# SwitchesStepAtten.net
KiCad netlist of a schematic drawn in EAGLE
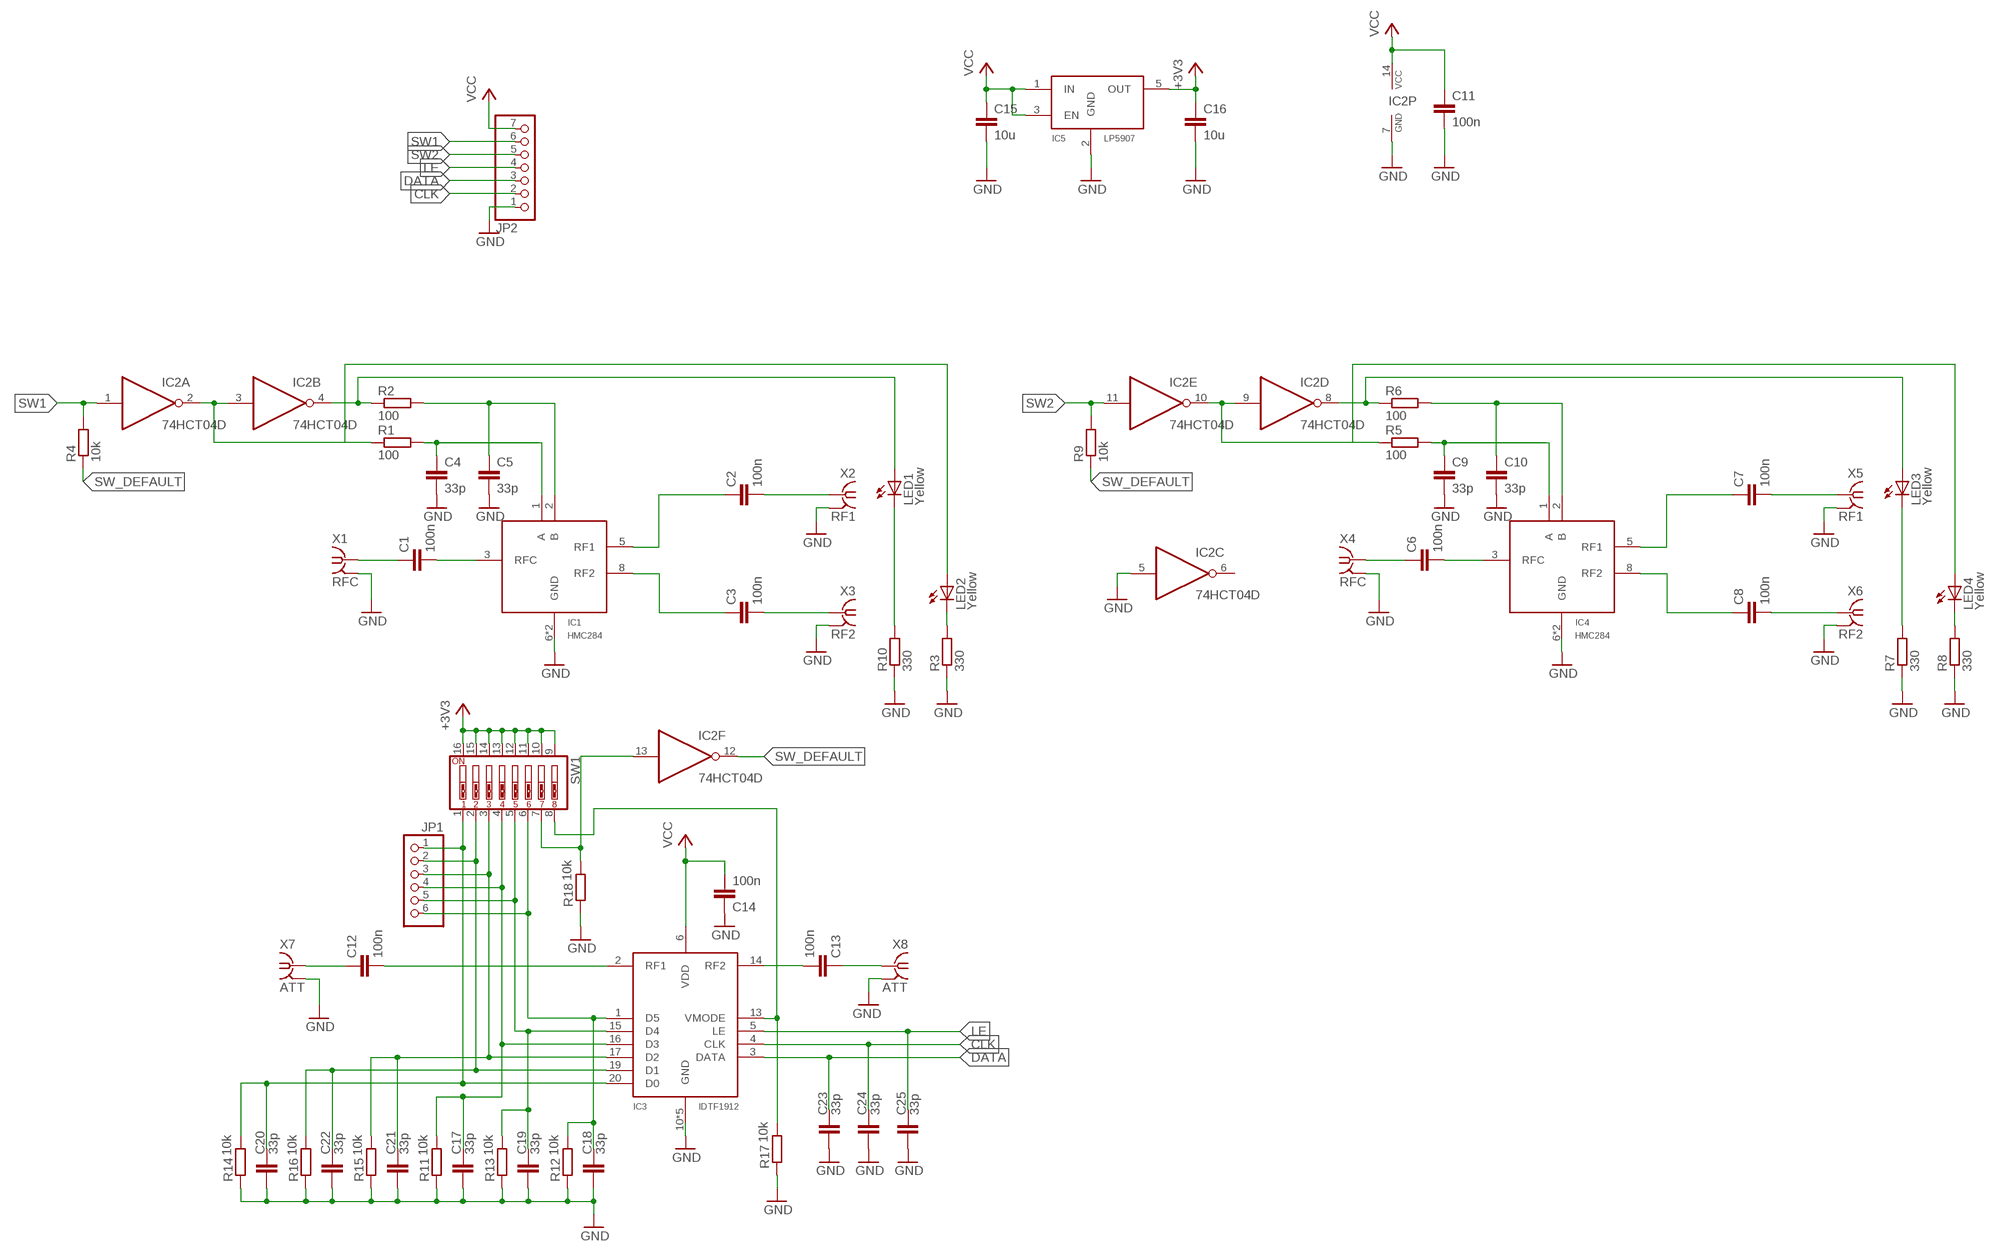
[diagram p0: schematic, sheet 1]

(export (version "E")
  (design (tool "Eeschema 10.0.6"))
  (components
    (comp (ref "C1")
      (value "100n")
      (footprint "eagle-import:C0603")
      (libsource (lib "eagle-import") (part "C-EUC0603"))
    )
    (comp (ref "C2")
      (value "100n")
      (footprint "eagle-import:C0603")
      (libsource (lib "eagle-import") (part "C-EUC0603"))
    )
    (comp (ref "C3")
      (value "100n")
      (footprint "eagle-import:C0603")
      (libsource (lib "eagle-import") (part "C-EUC0603"))
    )
    (comp (ref "C4")
      (value "33p")
      (footprint "eagle-import:C0603")
      (libsource (lib "eagle-import") (part "C-EUC0603"))
    )
    (comp (ref "C5")
      (value "33p")
      (footprint "eagle-import:C0603")
      (libsource (lib "eagle-import") (part "C-EUC0603"))
    )
    (comp (ref "C6")
      (value "100n")
      (footprint "eagle-import:C0603")
      (libsource (lib "eagle-import") (part "C-EUC0603"))
    )
    (comp (ref "C7")
      (value "100n")
      (footprint "eagle-import:C0603")
      (libsource (lib "eagle-import") (part "C-EUC0603"))
    )
    (comp (ref "C8")
      (value "100n")
      (footprint "eagle-import:C0603")
      (libsource (lib "eagle-import") (part "C-EUC0603"))
    )
    (comp (ref "C9")
      (value "33p")
      (footprint "eagle-import:C0603")
      (libsource (lib "eagle-import") (part "C-EUC0603"))
    )
    (comp (ref "C10")
      (value "33p")
      (footprint "eagle-import:C0603")
      (libsource (lib "eagle-import") (part "C-EUC0603"))
    )
    (comp (ref "C11")
      (value "100n")
      (footprint "eagle-import:C0603")
      (libsource (lib "eagle-import") (part "C-EUC0603"))
    )
    (comp (ref "C12")
      (value "100n")
      (footprint "eagle-import:C0603")
      (libsource (lib "eagle-import") (part "C-EUC0603"))
    )
    (comp (ref "C13")
      (value "100n")
      (footprint "eagle-import:C0603")
      (libsource (lib "eagle-import") (part "C-EUC0603"))
    )
    (comp (ref "C14")
      (value "100n")
      (footprint "eagle-import:C0603")
      (libsource (lib "eagle-import") (part "C-EUC0603"))
    )
    (comp (ref "C15")
      (value "10u")
      (footprint "eagle-import:C1206K")
      (libsource (lib "eagle-import") (part "resistor_C-EUC1206K"))
    )
    (comp (ref "C16")
      (value "10u")
      (footprint "eagle-import:C1206K")
      (libsource (lib "eagle-import") (part "resistor_C-EUC1206K"))
    )
    (comp (ref "C17")
      (value "33p")
      (footprint "eagle-import:C0603")
      (libsource (lib "eagle-import") (part "C-EUC0603"))
    )
    (comp (ref "C18")
      (value "33p")
      (footprint "eagle-import:C0603")
      (libsource (lib "eagle-import") (part "C-EUC0603"))
    )
    (comp (ref "C19")
      (value "33p")
      (footprint "eagle-import:C0603")
      (libsource (lib "eagle-import") (part "C-EUC0603"))
    )
    (comp (ref "C20")
      (value "33p")
      (footprint "eagle-import:C0603")
      (libsource (lib "eagle-import") (part "C-EUC0603"))
    )
    (comp (ref "C21")
      (value "33p")
      (footprint "eagle-import:C0603")
      (libsource (lib "eagle-import") (part "C-EUC0603"))
    )
    (comp (ref "C22")
      (value "33p")
      (footprint "eagle-import:C0603")
      (libsource (lib "eagle-import") (part "C-EUC0603"))
    )
    (comp (ref "C23")
      (value "33p")
      (footprint "eagle-import:C0603")
      (libsource (lib "eagle-import") (part "C-EUC0603"))
    )
    (comp (ref "C24")
      (value "33p")
      (footprint "eagle-import:C0603")
      (libsource (lib "eagle-import") (part "C-EUC0603"))
    )
    (comp (ref "C25")
      (value "33p")
      (footprint "eagle-import:C0603")
      (libsource (lib "eagle-import") (part "C-EUC0603"))
    )
    (comp (ref "IC1")
      (value "HMC284")
      (footprint "eagle-import:MSOP08")
      (libsource (lib "eagle-import") (part "HMC284"))
    )
    (comp (ref "IC2")
      (value "74HCT04D")
      (footprint "eagle-import:SO14")
      (libsource (lib "eagle-import") (part "7404DHCT"))
    )
    (comp (ref "IC3")
      (value "IDTF1912")
      (footprint "eagle-import:QFN50P400X400X75-21T206")
      (libsource (lib "eagle-import") (part "IDTF1912"))
    )
    (comp (ref "IC4")
      (value "HMC284")
      (footprint "eagle-import:MSOP08")
      (libsource (lib "eagle-import") (part "HMC284"))
    )
    (comp (ref "IC5")
      (value "LP5907")
      (footprint "eagle-import:SOT23-5L")
      (libsource (lib "eagle-import") (part "LP5907"))
    )
    (comp (ref "JP1")
      (value "PINHD-1X6")
      (footprint "eagle-import:1X06")
      (libsource (lib "eagle-import") (part "PINHD-1X6"))
    )
    (comp (ref "JP2")
      (value "PINHD-1X7/90")
      (footprint "eagle-import:1X07_90")
      (libsource (lib "eagle-import") (part "PINHD-1X7/90"))
    )
    (comp (ref "LED1")
      (value "Yellow")
      (footprint "eagle-import:LED_SML0603")
      (libsource (lib "eagle-import") (part "LED_ESML0603"))
    )
    (comp (ref "LED2")
      (value "Yellow")
      (footprint "eagle-import:LED_SML0603")
      (libsource (lib "eagle-import") (part "LED_ESML0603"))
    )
    (comp (ref "LED3")
      (value "Yellow")
      (footprint "eagle-import:LED_SML0603")
      (libsource (lib "eagle-import") (part "LED_ESML0603"))
    )
    (comp (ref "LED4")
      (value "Yellow")
      (footprint "eagle-import:LED_SML0603")
      (libsource (lib "eagle-import") (part "LED_ESML0603"))
    )
    (comp (ref "R1")
      (value "100")
      (footprint "eagle-import:R0603")
      (libsource (lib "eagle-import") (part "R-EU_R0603"))
    )
    (comp (ref "R2")
      (value "100")
      (footprint "eagle-import:R0603")
      (libsource (lib "eagle-import") (part "R-EU_R0603"))
    )
    (comp (ref "R3")
      (value "330")
      (footprint "eagle-import:R0603")
      (libsource (lib "eagle-import") (part "resistor_R-EU_R0603"))
    )
    (comp (ref "R4")
      (value "10k")
      (footprint "eagle-import:R0603")
      (libsource (lib "eagle-import") (part "resistor_R-EU_R0603"))
    )
    (comp (ref "R5")
      (value "100")
      (footprint "eagle-import:R0603")
      (libsource (lib "eagle-import") (part "R-EU_R0603"))
    )
    (comp (ref "R6")
      (value "100")
      (footprint "eagle-import:R0603")
      (libsource (lib "eagle-import") (part "R-EU_R0603"))
    )
    (comp (ref "R7")
      (value "330")
      (footprint "eagle-import:R0603")
      (libsource (lib "eagle-import") (part "resistor_R-EU_R0603"))
    )
    (comp (ref "R8")
      (value "330")
      (footprint "eagle-import:R0603")
      (libsource (lib "eagle-import") (part "resistor_R-EU_R0603"))
    )
    (comp (ref "R9")
      (value "10k")
      (footprint "eagle-import:R0603")
      (libsource (lib "eagle-import") (part "resistor_R-EU_R0603"))
    )
    (comp (ref "R10")
      (value "330")
      (footprint "eagle-import:R0603")
      (libsource (lib "eagle-import") (part "resistor_R-EU_R0603"))
    )
    (comp (ref "R11")
      (value "10k")
      (footprint "eagle-import:R0603")
      (libsource (lib "eagle-import") (part "resistor_R-EU_R0603"))
    )
    (comp (ref "R12")
      (value "10k")
      (footprint "eagle-import:R0603")
      (libsource (lib "eagle-import") (part "resistor_R-EU_R0603"))
    )
    (comp (ref "R13")
      (value "10k")
      (footprint "eagle-import:R0603")
      (libsource (lib "eagle-import") (part "resistor_R-EU_R0603"))
    )
    (comp (ref "R14")
      (value "10k")
      (footprint "eagle-import:R0603")
      (libsource (lib "eagle-import") (part "resistor_R-EU_R0603"))
    )
    (comp (ref "R15")
      (value "10k")
      (footprint "eagle-import:R0603")
      (libsource (lib "eagle-import") (part "resistor_R-EU_R0603"))
    )
    (comp (ref "R16")
      (value "10k")
      (footprint "eagle-import:R0603")
      (libsource (lib "eagle-import") (part "resistor_R-EU_R0603"))
    )
    (comp (ref "R17")
      (value "10k")
      (footprint "eagle-import:R0603")
      (libsource (lib "eagle-import") (part "resistor_R-EU_R0603"))
    )
    (comp (ref "R18")
      (value "10k")
      (footprint "eagle-import:R0603")
      (libsource (lib "eagle-import") (part "resistor_R-EU_R0603"))
    )
    (comp (ref "SW1")
      (value "SW_DIP-8")
      (footprint "eagle-import:EDG-08")
      (libsource (lib "eagle-import") (part "SW_DIP-8"))
    )
    (comp (ref "X1")
      (value "RFC")
      (footprint "eagle-import:J502-ND-142-0711-821_826")
      (libsource (lib "eagle-import") (part "SMA_CONNECTOR"))
    )
    (comp (ref "X2")
      (value "RF1")
      (footprint "eagle-import:J502-ND-142-0711-821_826")
      (libsource (lib "eagle-import") (part "SMA_CONNECTOR"))
    )
    (comp (ref "X3")
      (value "RF2")
      (footprint "eagle-import:J502-ND-142-0711-821_826")
      (libsource (lib "eagle-import") (part "SMA_CONNECTOR"))
    )
    (comp (ref "X4")
      (value "RFC")
      (footprint "eagle-import:J502-ND-142-0711-821_826")
      (libsource (lib "eagle-import") (part "SMA_CONNECTOR"))
    )
    (comp (ref "X5")
      (value "RF1")
      (footprint "eagle-import:J502-ND-142-0711-821_826")
      (libsource (lib "eagle-import") (part "SMA_CONNECTOR"))
    )
    (comp (ref "X6")
      (value "RF2")
      (footprint "eagle-import:J502-ND-142-0711-821_826")
      (libsource (lib "eagle-import") (part "SMA_CONNECTOR"))
    )
    (comp (ref "X7")
      (value "ATT")
      (footprint "eagle-import:J502-ND-142-0711-821_826")
      (libsource (lib "eagle-import") (part "SMA_CONNECTOR"))
    )
    (comp (ref "X8")
      (value "ATT")
      (footprint "eagle-import:J502-ND-142-0711-821_826")
      (libsource (lib "eagle-import") (part "SMA_CONNECTOR"))
    )
  )
  (nets
    (net (code "1") (name "+3V3") (class "Default")
      (node (ref "C16") (pin "1") (pinfunction "1_1") (pintype "passive"))
      (node (ref "IC5") (pin "5") (pinfunction "OUT_5") (pintype "bidirectional"))
      (node (ref "SW1") (pin "10") (pinfunction "10_10") (pintype "passive"))
      (node (ref "SW1") (pin "11") (pinfunction "11_11") (pintype "passive"))
      (node (ref "SW1") (pin "12") (pinfunction "12_12") (pintype "passive"))
      (node (ref "SW1") (pin "13") (pinfunction "13_13") (pintype "passive"))
      (node (ref "SW1") (pin "14") (pinfunction "14_14") (pintype "passive"))
      (node (ref "SW1") (pin "15") (pinfunction "15_15") (pintype "passive"))
      (node (ref "SW1") (pin "16") (pinfunction "16_16") (pintype "passive"))
      (node (ref "SW1") (pin "9") (pinfunction "9_9") (pintype "passive"))
    )
    (net (code "2") (name "CLK") (class "Default")
      (node (ref "C24") (pin "1") (pinfunction "1_1") (pintype "passive"))
      (node (ref "IC3") (pin "4") (pinfunction "CLK_4") (pintype "bidirectional"))
      (node (ref "JP2") (pin "2") (pinfunction "2_2") (pintype "passive"))
    )
    (net (code "3") (name "DATA") (class "Default")
      (node (ref "C23") (pin "1") (pinfunction "1_1") (pintype "passive"))
      (node (ref "IC3") (pin "3") (pinfunction "DATA_3") (pintype "bidirectional"))
      (node (ref "JP2") (pin "3") (pinfunction "3_3") (pintype "passive"))
    )
    (net (code "4") (name "GND") (class "Default")
      (node (ref "C10") (pin "2") (pinfunction "2_2") (pintype "passive"))
      (node (ref "C11") (pin "2") (pinfunction "2_2") (pintype "passive"))
      (node (ref "C14") (pin "1") (pinfunction "1_1") (pintype "passive"))
      (node (ref "C15") (pin "2") (pinfunction "2_2") (pintype "passive"))
      (node (ref "C16") (pin "2") (pinfunction "2_2") (pintype "passive"))
      (node (ref "C17") (pin "2") (pinfunction "2_2") (pintype "passive"))
      (node (ref "C18") (pin "2") (pinfunction "2_2") (pintype "passive"))
      (node (ref "C19") (pin "2") (pinfunction "2_2") (pintype "passive"))
      (node (ref "C20") (pin "2") (pinfunction "2_2") (pintype "passive"))
      (node (ref "C21") (pin "2") (pinfunction "2_2") (pintype "passive"))
      (node (ref "C22") (pin "2") (pinfunction "2_2") (pintype "passive"))
      (node (ref "C23") (pin "2") (pinfunction "2_2") (pintype "passive"))
      (node (ref "C24") (pin "2") (pinfunction "2_2") (pintype "passive"))
      (node (ref "C25") (pin "2") (pinfunction "2_2") (pintype "passive"))
      (node (ref "C4") (pin "2") (pinfunction "2_2") (pintype "passive"))
      (node (ref "C5") (pin "2") (pinfunction "2_2") (pintype "passive"))
      (node (ref "C9") (pin "2") (pinfunction "2_2") (pintype "passive"))
      (node (ref "IC1") (pin "6") (pinfunction "GND_6") (pintype "bidirectional"))
      (node (ref "IC1") (pin "7") (pinfunction "GND_7") (pintype "bidirectional"))
      (node (ref "IC2") (pin "5") (pinfunction "I_5") (pintype "input"))
      (node (ref "IC2") (pin "7") (pinfunction "GND_7") (pintype "power_in"))
      (node (ref "IC3") (pin "10") (pinfunction "GND_10") (pintype "bidirectional"))
      (node (ref "IC3") (pin "11") (pinfunction "GND_11") (pintype "bidirectional"))
      (node (ref "IC3") (pin "12") (pinfunction "GND_12") (pintype "bidirectional"))
      (node (ref "IC3") (pin "18") (pinfunction "GND_18") (pintype "bidirectional"))
      (node (ref "IC3") (pin "21") (pinfunction "GND_21") (pintype "bidirectional"))
      (node (ref "IC4") (pin "6") (pinfunction "GND_6") (pintype "bidirectional"))
      (node (ref "IC4") (pin "7") (pinfunction "GND_7") (pintype "bidirectional"))
      (node (ref "IC5") (pin "2") (pinfunction "GND_2") (pintype "bidirectional"))
      (node (ref "JP2") (pin "1") (pinfunction "1_1") (pintype "passive"))
      (node (ref "R10") (pin "1") (pinfunction "1_1") (pintype "passive"))
      (node (ref "R11") (pin "1") (pinfunction "1_1") (pintype "passive"))
      (node (ref "R12") (pin "1") (pinfunction "1_1") (pintype "passive"))
      (node (ref "R13") (pin "1") (pinfunction "1_1") (pintype "passive"))
      (node (ref "R14") (pin "1") (pinfunction "1_1") (pintype "passive"))
      (node (ref "R15") (pin "1") (pinfunction "1_1") (pintype "passive"))
      (node (ref "R16") (pin "1") (pinfunction "1_1") (pintype "passive"))
      (node (ref "R17") (pin "1") (pinfunction "1_1") (pintype "passive"))
      (node (ref "R18") (pin "1") (pinfunction "1_1") (pintype "passive"))
      (node (ref "R3") (pin "1") (pinfunction "1_1") (pintype "passive"))
      (node (ref "R7") (pin "1") (pinfunction "1_1") (pintype "passive"))
      (node (ref "R8") (pin "1") (pinfunction "1_1") (pintype "passive"))
      (node (ref "X1") (pin "G@1") (pinfunction "2_G@1") (pintype "passive"))
      (node (ref "X1") (pin "G@2") (pinfunction "2_G@2") (pintype "passive"))
      (node (ref "X1") (pin "G@3") (pinfunction "2_G@3") (pintype "passive"))
      (node (ref "X1") (pin "G@4") (pinfunction "2_G@4") (pintype "passive"))
      (node (ref "X2") (pin "G@1") (pinfunction "2_G@1") (pintype "passive"))
      (node (ref "X2") (pin "G@2") (pinfunction "2_G@2") (pintype "passive"))
      (node (ref "X2") (pin "G@3") (pinfunction "2_G@3") (pintype "passive"))
      (node (ref "X2") (pin "G@4") (pinfunction "2_G@4") (pintype "passive"))
      (node (ref "X3") (pin "G@1") (pinfunction "2_G@1") (pintype "passive"))
      (node (ref "X3") (pin "G@2") (pinfunction "2_G@2") (pintype "passive"))
      (node (ref "X3") (pin "G@3") (pinfunction "2_G@3") (pintype "passive"))
      (node (ref "X3") (pin "G@4") (pinfunction "2_G@4") (pintype "passive"))
      (node (ref "X4") (pin "G@1") (pinfunction "2_G@1") (pintype "passive"))
      (node (ref "X4") (pin "G@2") (pinfunction "2_G@2") (pintype "passive"))
      (node (ref "X4") (pin "G@3") (pinfunction "2_G@3") (pintype "passive"))
      (node (ref "X4") (pin "G@4") (pinfunction "2_G@4") (pintype "passive"))
      (node (ref "X5") (pin "G@1") (pinfunction "2_G@1") (pintype "passive"))
      (node (ref "X5") (pin "G@2") (pinfunction "2_G@2") (pintype "passive"))
      (node (ref "X5") (pin "G@3") (pinfunction "2_G@3") (pintype "passive"))
      (node (ref "X5") (pin "G@4") (pinfunction "2_G@4") (pintype "passive"))
      (node (ref "X6") (pin "G@1") (pinfunction "2_G@1") (pintype "passive"))
      (node (ref "X6") (pin "G@2") (pinfunction "2_G@2") (pintype "passive"))
      (node (ref "X6") (pin "G@3") (pinfunction "2_G@3") (pintype "passive"))
      (node (ref "X6") (pin "G@4") (pinfunction "2_G@4") (pintype "passive"))
      (node (ref "X7") (pin "G@1") (pinfunction "2_G@1") (pintype "passive"))
      (node (ref "X7") (pin "G@2") (pinfunction "2_G@2") (pintype "passive"))
      (node (ref "X7") (pin "G@3") (pinfunction "2_G@3") (pintype "passive"))
      (node (ref "X7") (pin "G@4") (pinfunction "2_G@4") (pintype "passive"))
      (node (ref "X8") (pin "G@1") (pinfunction "2_G@1") (pintype "passive"))
      (node (ref "X8") (pin "G@2") (pinfunction "2_G@2") (pintype "passive"))
      (node (ref "X8") (pin "G@3") (pinfunction "2_G@3") (pintype "passive"))
      (node (ref "X8") (pin "G@4") (pinfunction "2_G@4") (pintype "passive"))
    )
    (net (code "5") (name "LE") (class "Default")
      (node (ref "C25") (pin "1") (pinfunction "1_1") (pintype "passive"))
      (node (ref "IC3") (pin "5") (pinfunction "LE_5") (pintype "bidirectional"))
      (node (ref "JP2") (pin "4") (pinfunction "4_4") (pintype "passive"))
    )
    (net (code "6") (name "Net-(C1-Pad1)") (class "Default")
      (node (ref "C1") (pin "1") (pinfunction "1_1") (pintype "passive"))
      (node (ref "X1") (pin "1") (pinfunction "1_1") (pintype "passive"))
    )
    (net (code "7") (name "Net-(C2-Pad2)") (class "Default")
      (node (ref "C2") (pin "2") (pinfunction "2_2") (pintype "passive"))
      (node (ref "X2") (pin "1") (pinfunction "1_1") (pintype "passive"))
    )
    (net (code "8") (name "Net-(C3-Pad2)") (class "Default")
      (node (ref "C3") (pin "2") (pinfunction "2_2") (pintype "passive"))
      (node (ref "X3") (pin "1") (pinfunction "1_1") (pintype "passive"))
    )
    (net (code "9") (name "Net-(C6-Pad1)") (class "Default")
      (node (ref "C6") (pin "1") (pinfunction "1_1") (pintype "passive"))
      (node (ref "X4") (pin "1") (pinfunction "1_1") (pintype "passive"))
    )
    (net (code "10") (name "Net-(C7-Pad2)") (class "Default")
      (node (ref "C7") (pin "2") (pinfunction "2_2") (pintype "passive"))
      (node (ref "X5") (pin "1") (pinfunction "1_1") (pintype "passive"))
    )
    (net (code "11") (name "Net-(C8-Pad2)") (class "Default")
      (node (ref "C8") (pin "2") (pinfunction "2_2") (pintype "passive"))
      (node (ref "X6") (pin "1") (pinfunction "1_1") (pintype "passive"))
    )
    (net (code "12") (name "Net-(C12-Pad1)") (class "Default")
      (node (ref "C12") (pin "1") (pinfunction "1_1") (pintype "passive"))
      (node (ref "X7") (pin "1") (pinfunction "1_1") (pintype "passive"))
    )
    (net (code "13") (name "Net-(C13-Pad1)") (class "Default")
      (node (ref "C13") (pin "1") (pinfunction "1_1") (pintype "passive"))
      (node (ref "X8") (pin "1") (pinfunction "1_1") (pintype "passive"))
    )
    (net (code "14") (name "Net-(IC1-A)") (class "Default")
      (node (ref "C4") (pin "1") (pinfunction "1_1") (pintype "passive"))
      (node (ref "IC1") (pin "1") (pinfunction "A_1") (pintype "bidirectional"))
      (node (ref "R1") (pin "2") (pinfunction "2_2") (pintype "passive"))
    )
    (net (code "15") (name "Net-(IC1-B)") (class "Default")
      (node (ref "C5") (pin "1") (pinfunction "1_1") (pintype "passive"))
      (node (ref "IC1") (pin "2") (pinfunction "B_2") (pintype "bidirectional"))
      (node (ref "R2") (pin "2") (pinfunction "2_2") (pintype "passive"))
    )
    (net (code "16") (name "Net-(IC1-RF1)") (class "Default")
      (node (ref "C2") (pin "1") (pinfunction "1_1") (pintype "passive"))
      (node (ref "IC1") (pin "5") (pinfunction "RF1_5") (pintype "bidirectional"))
    )
    (net (code "17") (name "Net-(IC1-RF2)") (class "Default")
      (node (ref "C3") (pin "1") (pinfunction "1_1") (pintype "passive"))
      (node (ref "IC1") (pin "8") (pinfunction "RF2_8") (pintype "bidirectional"))
    )
    (net (code "18") (name "Net-(IC1-RFC)") (class "Default")
      (node (ref "C1") (pin "2") (pinfunction "2_2") (pintype "passive"))
      (node (ref "IC1") (pin "3") (pinfunction "RFC_3") (pintype "bidirectional"))
    )
    (net (code "19") (name "Net-(IC2A-O)") (class "Default")
      (node (ref "IC2") (pin "2") (pinfunction "O_2") (pintype "output"))
      (node (ref "IC2") (pin "3") (pinfunction "I_3") (pintype "input"))
      (node (ref "LED2") (pin "A") (pinfunction "A_A") (pintype "passive"))
      (node (ref "R1") (pin "1") (pinfunction "1_1") (pintype "passive"))
    )
    (net (code "20") (name "Net-(IC2B-O)") (class "Default")
      (node (ref "IC2") (pin "4") (pinfunction "O_4") (pintype "output"))
      (node (ref "LED1") (pin "A") (pinfunction "A_A") (pintype "passive"))
      (node (ref "R2") (pin "1") (pinfunction "1_1") (pintype "passive"))
    )
    (net (code "21") (name "Net-(IC2D-I)") (class "Default")
      (node (ref "IC2") (pin "10") (pinfunction "O_10") (pintype "output"))
      (node (ref "IC2") (pin "9") (pinfunction "I_9") (pintype "input"))
      (node (ref "LED4") (pin "A") (pinfunction "A_A") (pintype "passive"))
      (node (ref "R5") (pin "1") (pinfunction "1_1") (pintype "passive"))
    )
    (net (code "22") (name "Net-(IC2D-O)") (class "Default")
      (node (ref "IC2") (pin "8") (pinfunction "O_8") (pintype "output"))
      (node (ref "LED3") (pin "A") (pinfunction "A_A") (pintype "passive"))
      (node (ref "R6") (pin "1") (pinfunction "1_1") (pintype "passive"))
    )
    (net (code "23") (name "Net-(IC2F-I)") (class "Default")
      (node (ref "IC2") (pin "13") (pinfunction "I_13") (pintype "input"))
      (node (ref "R18") (pin "2") (pinfunction "2_2") (pintype "passive"))
      (node (ref "SW1") (pin "7") (pinfunction "7_7") (pintype "passive"))
    )
    (net (code "24") (name "Net-(IC3-D0)") (class "Default")
      (node (ref "C20") (pin "1") (pinfunction "1_1") (pintype "passive"))
      (node (ref "IC3") (pin "20") (pinfunction "D0_20") (pintype "bidirectional"))
      (node (ref "JP1") (pin "1") (pinfunction "1_1") (pintype "passive"))
      (node (ref "R14") (pin "2") (pinfunction "2_2") (pintype "passive"))
      (node (ref "SW1") (pin "1") (pinfunction "1_1") (pintype "passive"))
    )
    (net (code "25") (name "Net-(IC3-D1)") (class "Default")
      (node (ref "C22") (pin "1") (pinfunction "1_1") (pintype "passive"))
      (node (ref "IC3") (pin "19") (pinfunction "D1_19") (pintype "bidirectional"))
      (node (ref "JP1") (pin "2") (pinfunction "2_2") (pintype "passive"))
      (node (ref "R16") (pin "2") (pinfunction "2_2") (pintype "passive"))
      (node (ref "SW1") (pin "2") (pinfunction "2_2") (pintype "passive"))
    )
    (net (code "26") (name "Net-(IC3-D2)") (class "Default")
      (node (ref "C21") (pin "1") (pinfunction "1_1") (pintype "passive"))
      (node (ref "IC3") (pin "17") (pinfunction "D2_17") (pintype "bidirectional"))
      (node (ref "JP1") (pin "3") (pinfunction "3_3") (pintype "passive"))
      (node (ref "R15") (pin "2") (pinfunction "2_2") (pintype "passive"))
      (node (ref "SW1") (pin "3") (pinfunction "3_3") (pintype "passive"))
    )
    (net (code "27") (name "Net-(IC3-D3)") (class "Default")
      (node (ref "C17") (pin "1") (pinfunction "1_1") (pintype "passive"))
      (node (ref "IC3") (pin "16") (pinfunction "D3_16") (pintype "bidirectional"))
      (node (ref "JP1") (pin "4") (pinfunction "4_4") (pintype "passive"))
      (node (ref "R11") (pin "2") (pinfunction "2_2") (pintype "passive"))
      (node (ref "SW1") (pin "4") (pinfunction "4_4") (pintype "passive"))
    )
    (net (code "28") (name "Net-(IC3-D4)") (class "Default")
      (node (ref "C19") (pin "1") (pinfunction "1_1") (pintype "passive"))
      (node (ref "IC3") (pin "15") (pinfunction "D4_15") (pintype "bidirectional"))
      (node (ref "JP1") (pin "5") (pinfunction "5_5") (pintype "passive"))
      (node (ref "R13") (pin "2") (pinfunction "2_2") (pintype "passive"))
      (node (ref "SW1") (pin "5") (pinfunction "5_5") (pintype "passive"))
    )
    (net (code "29") (name "Net-(IC3-D5)") (class "Default")
      (node (ref "C18") (pin "1") (pinfunction "1_1") (pintype "passive"))
      (node (ref "IC3") (pin "1") (pinfunction "D5_1") (pintype "bidirectional"))
      (node (ref "JP1") (pin "6") (pinfunction "6_6") (pintype "passive"))
      (node (ref "R12") (pin "2") (pinfunction "2_2") (pintype "passive"))
      (node (ref "SW1") (pin "6") (pinfunction "6_6") (pintype "passive"))
    )
    (net (code "30") (name "Net-(IC3-RF1)") (class "Default")
      (node (ref "C12") (pin "2") (pinfunction "2_2") (pintype "passive"))
      (node (ref "IC3") (pin "2") (pinfunction "RF1_2") (pintype "bidirectional"))
    )
    (net (code "31") (name "Net-(IC3-RF2)") (class "Default")
      (node (ref "C13") (pin "2") (pinfunction "2_2") (pintype "passive"))
      (node (ref "IC3") (pin "14") (pinfunction "RF2_14") (pintype "bidirectional"))
    )
    (net (code "32") (name "Net-(IC3-VMODE)") (class "Default")
      (node (ref "IC3") (pin "13") (pinfunction "VMODE_13") (pintype "bidirectional"))
      (node (ref "R17") (pin "2") (pinfunction "2_2") (pintype "passive"))
      (node (ref "SW1") (pin "8") (pinfunction "8_8") (pintype "passive"))
    )
    (net (code "33") (name "Net-(IC4-A)") (class "Default")
      (node (ref "C9") (pin "1") (pinfunction "1_1") (pintype "passive"))
      (node (ref "IC4") (pin "1") (pinfunction "A_1") (pintype "bidirectional"))
      (node (ref "R5") (pin "2") (pinfunction "2_2") (pintype "passive"))
    )
    (net (code "34") (name "Net-(IC4-B)") (class "Default")
      (node (ref "C10") (pin "1") (pinfunction "1_1") (pintype "passive"))
      (node (ref "IC4") (pin "2") (pinfunction "B_2") (pintype "bidirectional"))
      (node (ref "R6") (pin "2") (pinfunction "2_2") (pintype "passive"))
    )
    (net (code "35") (name "Net-(IC4-RF1)") (class "Default")
      (node (ref "C7") (pin "1") (pinfunction "1_1") (pintype "passive"))
      (node (ref "IC4") (pin "5") (pinfunction "RF1_5") (pintype "bidirectional"))
    )
    (net (code "36") (name "Net-(IC4-RF2)") (class "Default")
      (node (ref "C8") (pin "1") (pinfunction "1_1") (pintype "passive"))
      (node (ref "IC4") (pin "8") (pinfunction "RF2_8") (pintype "bidirectional"))
    )
    (net (code "37") (name "Net-(IC4-RFC)") (class "Default")
      (node (ref "C6") (pin "2") (pinfunction "2_2") (pintype "passive"))
      (node (ref "IC4") (pin "3") (pinfunction "RFC_3") (pintype "bidirectional"))
    )
    (net (code "38") (name "Net-(LED1-PadC)") (class "Default")
      (node (ref "LED1") (pin "C") (pinfunction "C_C") (pintype "passive"))
      (node (ref "R10") (pin "2") (pinfunction "2_2") (pintype "passive"))
    )
    (net (code "39") (name "Net-(LED2-PadC)") (class "Default")
      (node (ref "LED2") (pin "C") (pinfunction "C_C") (pintype "passive"))
      (node (ref "R3") (pin "2") (pinfunction "2_2") (pintype "passive"))
    )
    (net (code "40") (name "Net-(LED3-PadC)") (class "Default")
      (node (ref "LED3") (pin "C") (pinfunction "C_C") (pintype "passive"))
      (node (ref "R7") (pin "2") (pinfunction "2_2") (pintype "passive"))
    )
    (net (code "41") (name "Net-(LED4-PadC)") (class "Default")
      (node (ref "LED4") (pin "C") (pinfunction "C_C") (pintype "passive"))
      (node (ref "R8") (pin "2") (pinfunction "2_2") (pintype "passive"))
    )
    (net (code "42") (name "SW1") (class "Default")
      (node (ref "IC2") (pin "1") (pinfunction "I_1") (pintype "input"))
      (node (ref "JP2") (pin "6") (pinfunction "6_6") (pintype "passive"))
      (node (ref "R4") (pin "2") (pinfunction "2_2") (pintype "passive"))
    )
    (net (code "43") (name "SW2") (class "Default")
      (node (ref "IC2") (pin "11") (pinfunction "I_11") (pintype "input"))
      (node (ref "JP2") (pin "5") (pinfunction "5_5") (pintype "passive"))
      (node (ref "R9") (pin "2") (pinfunction "2_2") (pintype "passive"))
    )
    (net (code "44") (name "SW_DEFAULT") (class "Default")
      (node (ref "IC2") (pin "12") (pinfunction "O_12") (pintype "output"))
      (node (ref "R4") (pin "1") (pinfunction "1_1") (pintype "passive"))
      (node (ref "R9") (pin "1") (pinfunction "1_1") (pintype "passive"))
    )
    (net (code "45") (name "VCC") (class "Default")
      (node (ref "C11") (pin "1") (pinfunction "1_1") (pintype "passive"))
      (node (ref "C14") (pin "2") (pinfunction "2_2") (pintype "passive"))
      (node (ref "C15") (pin "1") (pinfunction "1_1") (pintype "passive"))
      (node (ref "IC2") (pin "14") (pinfunction "VCC_14") (pintype "power_in"))
      (node (ref "IC3") (pin "6") (pinfunction "VDD_6") (pintype "bidirectional"))
      (node (ref "IC5") (pin "1") (pinfunction "IN_1") (pintype "bidirectional"))
      (node (ref "IC5") (pin "3") (pinfunction "EN_3") (pintype "bidirectional"))
      (node (ref "JP2") (pin "7") (pinfunction "7_7") (pintype "passive"))
    )
    (net (code "46") (name "unconnected-(IC2C-O-Pad6)") (class "Default")
      (node (ref "IC2") (pin "6") (pinfunction "O_6") (pintype "output"))
    )
  )
)
